# Grove_-_6-Axis_Accelerometer_Compass.net
KiCad netlist of a schematic drawn in EAGLE
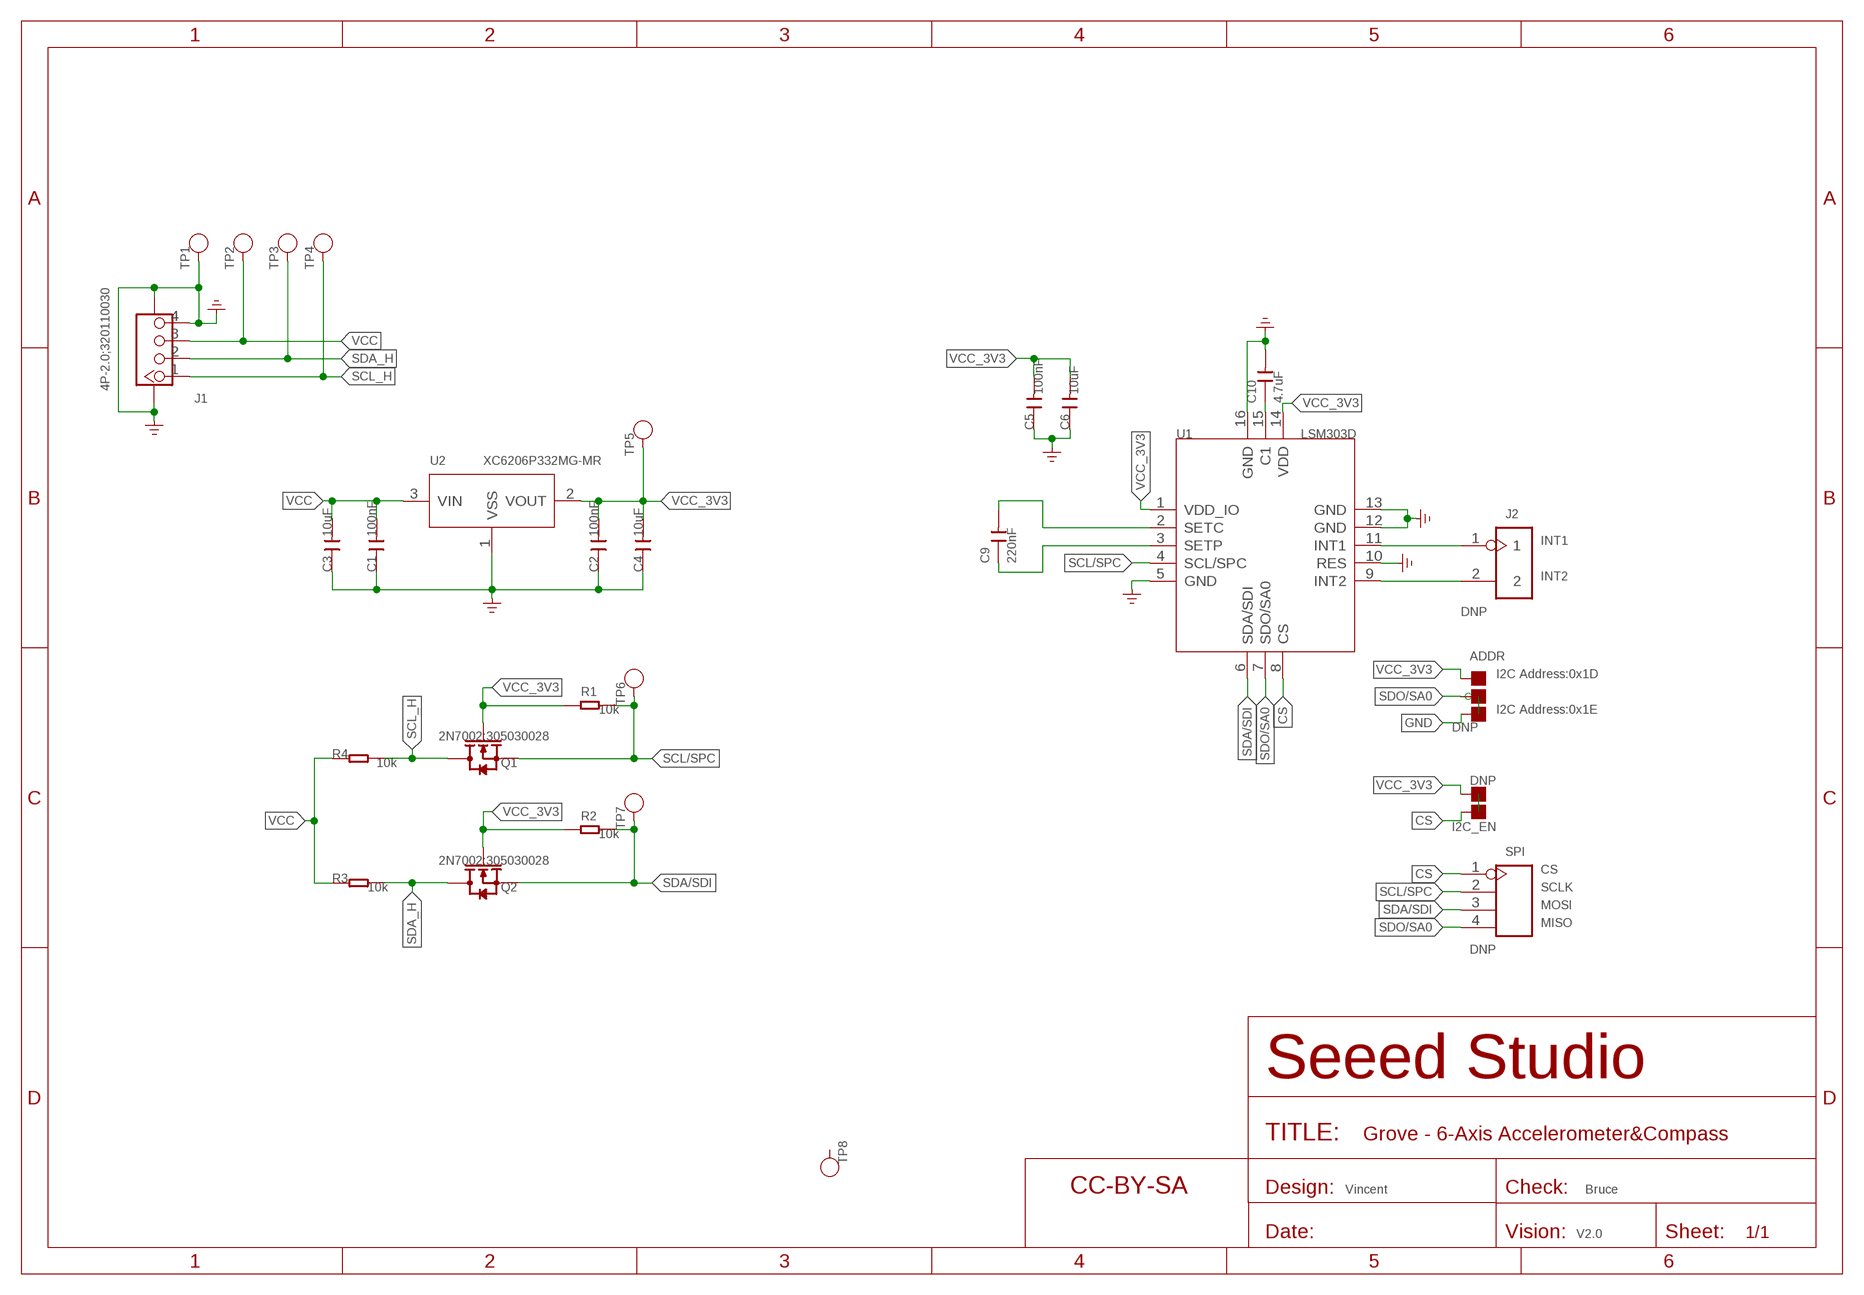
[diagram p0: schematic, sheet 1]

(export (version "E")
  (design (tool "Eeschema 10.0.6"))
  (components
    (comp (ref "ADDR")
      (value "DNP")
      (footprint "eagle-import:3P-SMD-L4.1_W1.5MM")
      (libsource (lib "eagle-import") (part "PAD-JUMPER-3P-4040"))
    )
    (comp (ref "C1")
      (value "100nF")
      (footprint "eagle-import:C0603")
      (libsource (lib "eagle-import") (part "CAP-0603"))
    )
    (comp (ref "C2")
      (value "100nF")
      (footprint "eagle-import:C0603")
      (libsource (lib "eagle-import") (part "CAP-0603"))
    )
    (comp (ref "C3")
      (value "10uF")
      (footprint "eagle-import:C0805")
      (libsource (lib "eagle-import") (part "CAP-0805"))
    )
    (comp (ref "C4")
      (value "10uF")
      (footprint "eagle-import:C0805")
      (libsource (lib "eagle-import") (part "CAP-0805"))
    )
    (comp (ref "C5")
      (value "100nF")
      (footprint "eagle-import:C0603")
      (libsource (lib "eagle-import") (part "CAP-0603"))
    )
    (comp (ref "C6")
      (value "10uF")
      (footprint "eagle-import:C0805")
      (libsource (lib "eagle-import") (part "CAP-0805"))
    )
    (comp (ref "C9")
      (value "220nF")
      (footprint "eagle-import:C0603")
      (libsource (lib "eagle-import") (part "CAP-0603"))
    )
    (comp (ref "C10")
      (value "4.7uF")
      (footprint "eagle-import:C0603")
      (libsource (lib "eagle-import") (part "CAP-0603"))
    )
    (comp (ref "I2C_EN")
      (value "DNP")
      (footprint "eagle-import:2P-SMD-L1.78_W1.27MM")
      (libsource (lib "eagle-import") (part "PAD-JUMPER-2P"))
    )
    (comp (ref "J1")
      (value "4P-2.0;320110030")
      (footprint "eagle-import:4P-SMD-2.0")
      (libsource (lib "eagle-import") (part "GROVE-CONNECTOR-SMD'DD'"))
    )
    (comp (ref "J2")
      (value "DNP")
      (footprint "eagle-import:2P-2.54-65_35MIL")
      (libsource (lib "eagle-import") (part "HEADER-2P-65/35MIL"))
    )
    (comp (ref "Q1")
      (value "2N7002;305030028")
      (footprint "eagle-import:SOT-23")
      (libsource (lib "eagle-import") (part "MOSFET-N'SOT23'"))
    )
    (comp (ref "Q2")
      (value "2N7002;305030028")
      (footprint "eagle-import:SOT-23")
      (libsource (lib "eagle-import") (part "MOSFET-N'SOT23'"))
    )
    (comp (ref "R1")
      (value "10k")
      (footprint "eagle-import:R0603")
      (libsource (lib "eagle-import") (part "RES-0603"))
    )
    (comp (ref "R2")
      (value "10k")
      (footprint "eagle-import:R0603")
      (libsource (lib "eagle-import") (part "RES-0603"))
    )
    (comp (ref "R3")
      (value "10k")
      (footprint "eagle-import:R0603")
      (libsource (lib "eagle-import") (part "RES-0603"))
    )
    (comp (ref "R4")
      (value "10k")
      (footprint "eagle-import:R0603")
      (libsource (lib "eagle-import") (part "RES-0603"))
    )
    (comp (ref "SPI")
      (value "DNP")
      (footprint "eagle-import:4P-2.54-65_35MIL")
      (libsource (lib "eagle-import") (part "HEADER-4P-65/35MIL"))
    )
    (comp (ref "TP1")
      (value "DNP")
      (footprint "eagle-import:TP-D45MIL")
      (libsource (lib "eagle-import") (part "PAD-TEST-POINT'4545'"))
    )
    (comp (ref "TP2")
      (value "DNP")
      (footprint "eagle-import:TP-D45MIL")
      (libsource (lib "eagle-import") (part "PAD-TEST-POINT'4545'"))
    )
    (comp (ref "TP3")
      (value "DNP")
      (footprint "eagle-import:TP-D45MIL")
      (libsource (lib "eagle-import") (part "PAD-TEST-POINT'4545'"))
    )
    (comp (ref "TP4")
      (value "DNP")
      (footprint "eagle-import:TP-D45MIL")
      (libsource (lib "eagle-import") (part "PAD-TEST-POINT'4545'"))
    )
    (comp (ref "TP5")
      (value "DNP")
      (footprint "eagle-import:TP-D45MIL")
      (libsource (lib "eagle-import") (part "PAD-TEST-POINT'4545'"))
    )
    (comp (ref "TP6")
      (value "DNP")
      (footprint "eagle-import:TP-D45MIL")
      (libsource (lib "eagle-import") (part "PAD-TEST-POINT'4545'"))
    )
    (comp (ref "TP7")
      (value "DNP")
      (footprint "eagle-import:TP-D45MIL")
      (libsource (lib "eagle-import") (part "PAD-TEST-POINT'4545'"))
    )
    (comp (ref "TP8")
      (value "DNP")
      (footprint "eagle-import:TP-D45MIL")
      (libsource (lib "eagle-import") (part "PAD-TEST-POINT'4545'"))
    )
    (comp (ref "U$1")
      (value "SEEEDSTUDIO-OPEN-SCH-FRAME")
      (footprint "eagle-import:SEEEDSTUDIO-PCB-FRAME")
      (libsource (lib "eagle-import") (part "SEEEDSTUDIO-OPEN-SCH-FRAME"))
    )
    (comp (ref "U1")
      (value "LSM303D")
      (footprint "eagle-import:LGA-16")
      (libsource (lib "eagle-import") (part "LSM303D"))
    )
    (comp (ref "U2")
      (value "XC6206P332MG-MR")
      (footprint "eagle-import:SOT-23")
      (libsource (lib "eagle-import") (part "PMIC-XC6206PMR"))
    )
  )
  (nets
    (net (code "1") (name "CS") (class "Default")
      (node (ref "I2C_EN") (pin "2") (pinfunction "2_2") (pintype "bidirectional"))
      (node (ref "SPI") (pin "1") (pinfunction "P$1_1") (pintype "bidirectional"))
      (node (ref "U1") (pin "8") (pinfunction "CS_8") (pintype "bidirectional"))
    )
    (net (code "2") (name "GND") (class "Default")
      (node (ref "ADDR") (pin "11") (pinfunction "R_11") (pintype "bidirectional"))
      (node (ref "C1") (pin "1") (pinfunction "1_1") (pintype "passive"))
      (node (ref "C10") (pin "2") (pinfunction "2_2") (pintype "passive"))
      (node (ref "C2") (pin "1") (pinfunction "1_1") (pintype "passive"))
      (node (ref "C3") (pin "1") (pinfunction "1_1") (pintype "passive"))
      (node (ref "C4") (pin "1") (pinfunction "1_1") (pintype "passive"))
      (node (ref "C5") (pin "1") (pinfunction "1_1") (pintype "passive"))
      (node (ref "C6") (pin "1") (pinfunction "1_1") (pintype "passive"))
      (node (ref "J1") (pin "4") (pinfunction "4_4") (pintype "bidirectional"))
      (node (ref "J1") (pin "SS1") (pinfunction "SS1_SS1") (pintype "bidirectional"))
      (node (ref "J1") (pin "SS2") (pinfunction "SS2_SS2") (pintype "bidirectional"))
      (node (ref "TP1") (pin "T") (pinfunction "T_T") (pintype "bidirectional"))
      (node (ref "U1") (pin "10") (pinfunction "RES_10") (pintype "bidirectional"))
      (node (ref "U1") (pin "12") (pinfunction "GND_12") (pintype "bidirectional"))
      (node (ref "U1") (pin "13") (pinfunction "GND_13") (pintype "bidirectional"))
      (node (ref "U1") (pin "16") (pinfunction "GND_16") (pintype "bidirectional"))
      (node (ref "U1") (pin "5") (pinfunction "GND_5") (pintype "bidirectional"))
      (node (ref "U2") (pin "1") (pinfunction "VSS_1") (pintype "power_in"))
    )
    (net (code "3") (name "Net-(U1-C1)") (class "Default")
      (node (ref "C10") (pin "1") (pinfunction "1_1") (pintype "passive"))
      (node (ref "U1") (pin "15") (pinfunction "C1_15") (pintype "bidirectional"))
    )
    (net (code "4") (name "Net-(U1-INT1)") (class "Default")
      (node (ref "J2") (pin "1") (pinfunction "1_1") (pintype "bidirectional"))
      (node (ref "U1") (pin "11") (pinfunction "INT1_11") (pintype "bidirectional"))
    )
    (net (code "5") (name "Net-(U1-INT2)") (class "Default")
      (node (ref "J2") (pin "2") (pinfunction "2_2") (pintype "bidirectional"))
      (node (ref "U1") (pin "9") (pinfunction "INT2_9") (pintype "bidirectional"))
    )
    (net (code "6") (name "Net-(U1-SETC)") (class "Default")
      (node (ref "C9") (pin "2") (pinfunction "2_2") (pintype "passive"))
      (node (ref "U1") (pin "2") (pinfunction "SETC_2") (pintype "bidirectional"))
    )
    (net (code "7") (name "Net-(U1-SETP)") (class "Default")
      (node (ref "C9") (pin "1") (pinfunction "1_1") (pintype "passive"))
      (node (ref "U1") (pin "3") (pinfunction "SETP_3") (pintype "bidirectional"))
    )
    (net (code "8") (name "SCL_H") (class "Default")
      (node (ref "J1") (pin "1") (pinfunction "1_1") (pintype "bidirectional"))
      (node (ref "Q1") (pin "3") (pinfunction "D_3") (pintype "passive"))
      (node (ref "R4") (pin "2") (pinfunction "2_2") (pintype "passive"))
      (node (ref "TP4") (pin "T") (pinfunction "T_T") (pintype "bidirectional"))
    )
    (net (code "9") (name "SCL{slash}SPC") (class "Default")
      (node (ref "Q1") (pin "2") (pinfunction "S_2") (pintype "passive"))
      (node (ref "R1") (pin "2") (pinfunction "2_2") (pintype "passive"))
      (node (ref "SPI") (pin "2") (pinfunction "P$2_2") (pintype "bidirectional"))
      (node (ref "TP6") (pin "T") (pinfunction "T_T") (pintype "bidirectional"))
      (node (ref "U1") (pin "4") (pinfunction "SCL/SPC_4") (pintype "bidirectional"))
    )
    (net (code "10") (name "SDA_H") (class "Default")
      (node (ref "J1") (pin "2") (pinfunction "2_2") (pintype "bidirectional"))
      (node (ref "Q2") (pin "3") (pinfunction "D_3") (pintype "passive"))
      (node (ref "R3") (pin "2") (pinfunction "2_2") (pintype "passive"))
      (node (ref "TP3") (pin "T") (pinfunction "T_T") (pintype "bidirectional"))
    )
    (net (code "11") (name "SDA{slash}SDI") (class "Default")
      (node (ref "Q2") (pin "2") (pinfunction "S_2") (pintype "passive"))
      (node (ref "R2") (pin "2") (pinfunction "2_2") (pintype "passive"))
      (node (ref "SPI") (pin "3") (pinfunction "P$3_3") (pintype "bidirectional"))
      (node (ref "TP7") (pin "T") (pinfunction "T_T") (pintype "bidirectional"))
      (node (ref "U1") (pin "6") (pinfunction "SDA/SDI_6") (pintype "bidirectional"))
    )
    (net (code "12") (name "SDO{slash}SA0") (class "Default")
      (node (ref "ADDR") (pin "MM") (pinfunction "C_MM") (pintype "bidirectional"))
      (node (ref "SPI") (pin "4") (pinfunction "P$4_4") (pintype "bidirectional"))
      (node (ref "U1") (pin "7") (pinfunction "SDO/SA0_7") (pintype "bidirectional"))
    )
    (net (code "13") (name "VCC") (class "Default")
      (node (ref "C1") (pin "2") (pinfunction "2_2") (pintype "passive"))
      (node (ref "C3") (pin "2") (pinfunction "2_2") (pintype "passive"))
      (node (ref "J1") (pin "3") (pinfunction "3_3") (pintype "bidirectional"))
      (node (ref "R3") (pin "1") (pinfunction "1_1") (pintype "passive"))
      (node (ref "R4") (pin "1") (pinfunction "1_1") (pintype "passive"))
      (node (ref "TP2") (pin "T") (pinfunction "T_T") (pintype "bidirectional"))
      (node (ref "U2") (pin "3") (pinfunction "VIN_3") (pintype "input"))
    )
    (net (code "14") (name "VCC_3V3") (class "Default")
      (node (ref "ADDR") (pin "00") (pinfunction "L_00") (pintype "bidirectional"))
      (node (ref "C2") (pin "2") (pinfunction "2_2") (pintype "passive"))
      (node (ref "C4") (pin "2") (pinfunction "2_2") (pintype "passive"))
      (node (ref "C5") (pin "2") (pinfunction "2_2") (pintype "passive"))
      (node (ref "C6") (pin "2") (pinfunction "2_2") (pintype "passive"))
      (node (ref "I2C_EN") (pin "1") (pinfunction "1_1") (pintype "bidirectional"))
      (node (ref "Q1") (pin "1") (pinfunction "G_1") (pintype "passive"))
      (node (ref "Q2") (pin "1") (pinfunction "G_1") (pintype "passive"))
      (node (ref "R1") (pin "1") (pinfunction "1_1") (pintype "passive"))
      (node (ref "R2") (pin "1") (pinfunction "1_1") (pintype "passive"))
      (node (ref "TP5") (pin "T") (pinfunction "T_T") (pintype "bidirectional"))
      (node (ref "U1") (pin "1") (pinfunction "VDD_IO_1") (pintype "bidirectional"))
      (node (ref "U1") (pin "14") (pinfunction "VDD_14") (pintype "bidirectional"))
      (node (ref "U2") (pin "2") (pinfunction "VOUT_2") (pintype "output"))
    )
    (net (code "15") (name "unconnected-(TP8-PadT)") (class "Default")
      (node (ref "TP8") (pin "T") (pinfunction "T_T") (pintype "bidirectional"))
    )
  )
)
